# CPU.net
KiCad netlist of a schematic drawn in Altium Designer
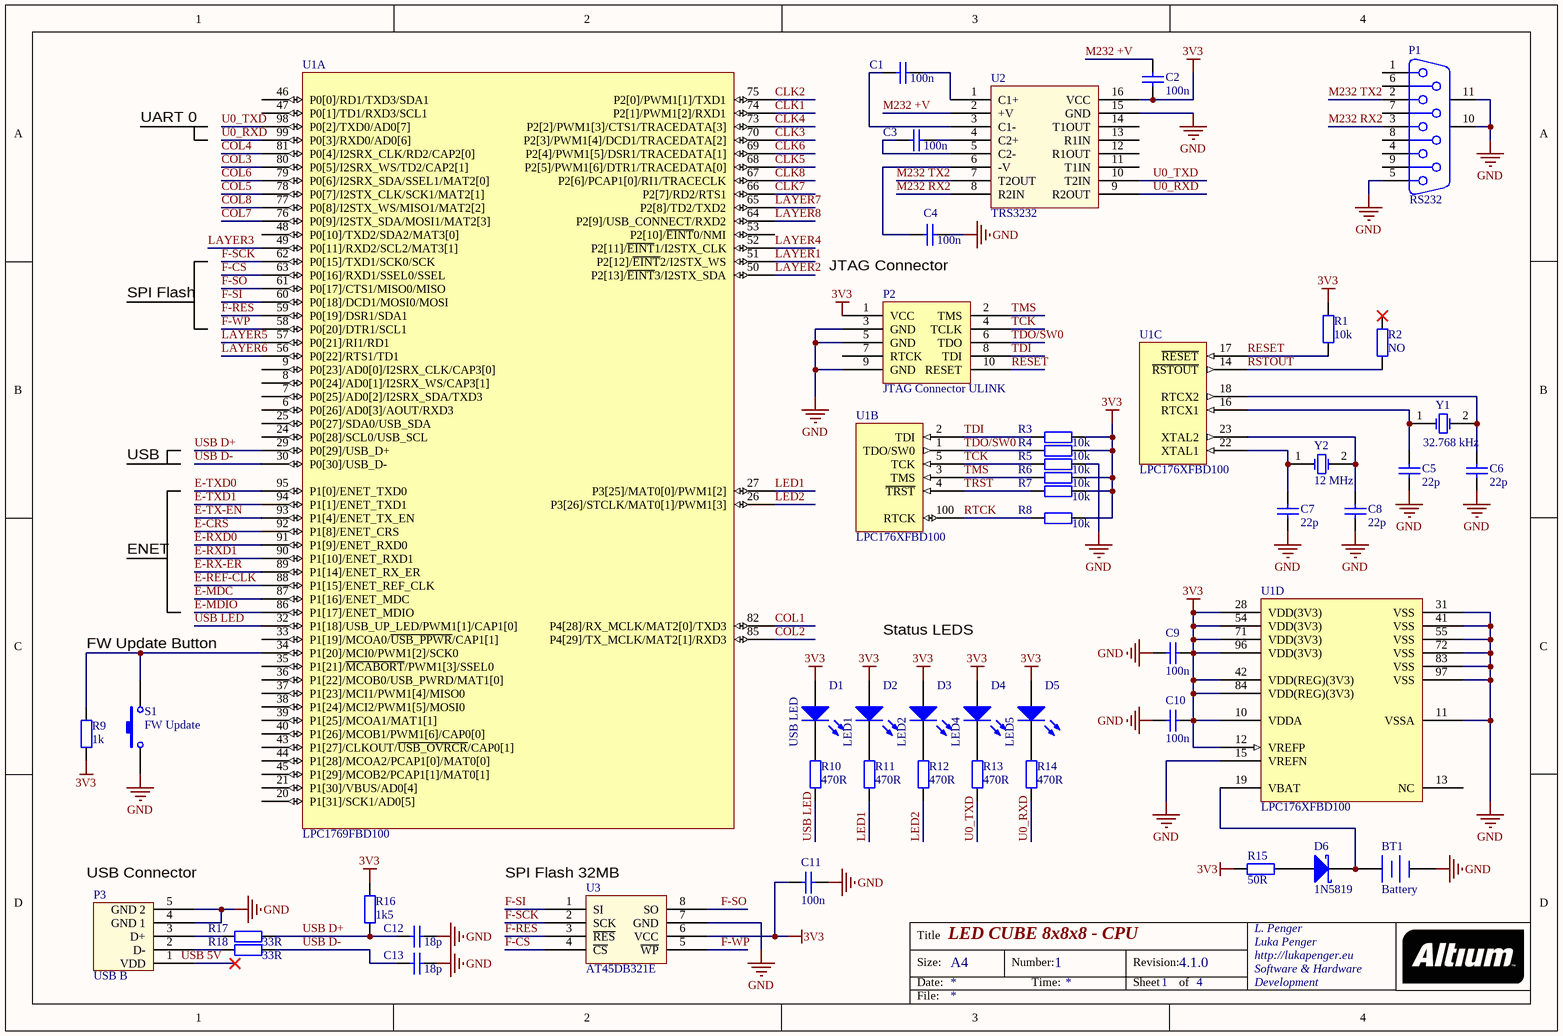
[diagram p0: CPU.SchDoc]

(export (version "E")
  (design (tool "Eeschema 10.0.6"))
  (components
    (comp (ref "BT1")
      (value "Battery")
      (footprint "Battery capacitor")
      (description "Multicell Battery")
      (fields (field (name "PUBLISHER") "Altium Limited"))
      (libsource (lib "Miscellaneous Devices") (part "Battery"))
    )
    (comp (ref "C1")
      (value "100n")
      (footprint "1608[0603]")
      (description "Capacitor")
      (fields (field (name "PUBLISHER") "Altium Limited"))
      (libsource (lib "Miscellaneous Devices") (part "Cap"))
    )
    (comp (ref "C2")
      (value "100n")
      (footprint "1608[0603]")
      (description "Capacitor")
      (fields (field (name "PUBLISHER") "Altium Limited"))
      (libsource (lib "Miscellaneous Devices") (part "Cap"))
    )
    (comp (ref "C3")
      (value "100n")
      (footprint "1608[0603]")
      (description "Capacitor")
      (fields (field (name "PUBLISHER") "Altium Limited"))
      (libsource (lib "Miscellaneous Devices") (part "Cap"))
    )
    (comp (ref "C4")
      (value "100n")
      (footprint "1608[0603]")
      (description "Capacitor")
      (fields (field (name "PUBLISHER") "Altium Limited"))
      (libsource (lib "Miscellaneous Devices") (part "Cap"))
    )
    (comp (ref "C5")
      (value "22p")
      (footprint "1608[0603]")
      (description "Capacitor")
      (fields (field (name "PUBLISHER") "Altium Limited"))
      (libsource (lib "Miscellaneous Devices") (part "Cap"))
    )
    (comp (ref "C6")
      (value "22p")
      (footprint "1608[0603]")
      (description "Capacitor")
      (fields (field (name "PUBLISHER") "Altium Limited"))
      (libsource (lib "Miscellaneous Devices") (part "Cap"))
    )
    (comp (ref "C7")
      (value "22p")
      (footprint "1608[0603]")
      (description "Capacitor")
      (fields (field (name "PUBLISHER") "Altium Limited"))
      (libsource (lib "Miscellaneous Devices") (part "Cap"))
    )
    (comp (ref "C8")
      (value "22p")
      (footprint "1608[0603]")
      (description "Capacitor")
      (fields (field (name "PUBLISHER") "Altium Limited"))
      (libsource (lib "Miscellaneous Devices") (part "Cap"))
    )
    (comp (ref "C9")
      (value "100n")
      (footprint "1608[0603]")
      (description "Capacitor")
      (fields (field (name "PUBLISHER") "Altium Limited"))
      (libsource (lib "Miscellaneous Devices") (part "Cap"))
    )
    (comp (ref "C10")
      (value "100n")
      (footprint "1608[0603]")
      (description "Capacitor")
      (fields (field (name "PUBLISHER") "Altium Limited"))
      (libsource (lib "Miscellaneous Devices") (part "Cap"))
    )
    (comp (ref "C11")
      (value "100n")
      (footprint "1608[0603]")
      (description "Capacitor")
      (fields (field (name "PUBLISHER") "Altium Limited"))
      (libsource (lib "Miscellaneous Devices") (part "Cap"))
    )
    (comp (ref "C12")
      (value "18p")
      (footprint "1608[0603]")
      (description "Capacitor")
      (fields (field (name "PUBLISHER") "Altium Limited"))
      (libsource (lib "Miscellaneous Devices") (part "Cap"))
    )
    (comp (ref "C13")
      (value "18p")
      (footprint "1608[0603]")
      (description "Capacitor")
      (fields (field (name "PUBLISHER") "Altium Limited"))
      (libsource (lib "Miscellaneous Devices") (part "Cap"))
    )
    (comp (ref "D1")
      (value "USB LED")
      (footprint "LED-1")
      (description "Typical INFRARED GaAs LED")
      (fields (field (name "PUBLISHER") "Altium Limited"))
      (libsource (lib "Miscellaneous Devices") (part "LED0"))
    )
    (comp (ref "D2")
      (value "LED1")
      (footprint "LED-1")
      (description "Typical INFRARED GaAs LED")
      (fields (field (name "PUBLISHER") "Altium Limited"))
      (libsource (lib "Miscellaneous Devices") (part "LED0"))
    )
    (comp (ref "D3")
      (value "LED2")
      (footprint "LED-1")
      (description "Typical INFRARED GaAs LED")
      (fields (field (name "PUBLISHER") "Altium Limited"))
      (libsource (lib "Miscellaneous Devices") (part "LED0"))
    )
    (comp (ref "D4")
      (value "LED4")
      (footprint "LED-1")
      (description "Typical INFRARED GaAs LED")
      (fields (field (name "PUBLISHER") "Altium Limited"))
      (libsource (lib "Miscellaneous Devices") (part "LED0"))
    )
    (comp (ref "D5")
      (value "LED5")
      (footprint "LED-1")
      (description "Typical INFRARED GaAs LED")
      (fields (field (name "PUBLISHER") "Altium Limited"))
      (libsource (lib "Miscellaneous Devices") (part "LED0"))
    )
    (comp (ref "D6")
      (value "1N5819")
      (footprint "DO-214AC (SMA)")
      (description "Schottky Diode")
      (fields (field (name "PUBLISHER") "Altium Limited"))
      (libsource (lib "Miscellaneous Devices") (part "D Schottky"))
    )
    (comp (ref "P1")
      (value "RS232")
      (footprint "DSUB1.385-2H9")
      (description "Receptacle Assembly, 9 Position, Right Angle")
      (fields (field (name "PUBLISHER") "Altium Limited"))
      (libsource (lib "Miscellaneous Connectors") (part "D Connector 9"))
    )
    (comp (ref "P2")
      (value "JTAG Connector ULINK")
      (footprint "SMT IDC Header 2X5 10 PIN 1.27mm")
      (description "JTAG Connector")
      (libsource (lib "LP_Lib") (part "JTAG Connector ULINK"))
    )
    (comp (ref "P3")
      (value "USB B")
      (footprint "USB B")
      (description "USB Connector")
      (libsource (lib "LP_Lib") (part "USB B"))
    )
    (comp (ref "R1")
      (value "10k")
      (footprint "1608[0603]")
      (description "Resistor")
      (fields (field (name "PUBLISHER") "Altium Limited"))
      (libsource (lib "Miscellaneous Devices") (part "Res2"))
    )
    (comp (ref "R2")
      (value "NO")
      (footprint "1608[0603]")
      (description "Resistor")
      (fields (field (name "PUBLISHER") "Altium Limited"))
      (libsource (lib "Miscellaneous Devices") (part "Res2"))
    )
    (comp (ref "R3")
      (value "10k")
      (footprint "1608[0603]")
      (description "Resistor")
      (fields (field (name "PUBLISHER") "Altium Limited"))
      (libsource (lib "") (part "Res2_3"))
    )
    (comp (ref "R4")
      (value "10k")
      (footprint "1608[0603]")
      (description "Resistor")
      (fields (field (name "PUBLISHER") "Altium Limited"))
      (libsource (lib "") (part "Res2_3"))
    )
    (comp (ref "R5")
      (value "10k")
      (footprint "1608[0603]")
      (description "Resistor")
      (fields (field (name "PUBLISHER") "Altium Limited"))
      (libsource (lib "") (part "Res2_3"))
    )
    (comp (ref "R6")
      (value "10k")
      (footprint "1608[0603]")
      (description "Resistor")
      (fields (field (name "PUBLISHER") "Altium Limited"))
      (libsource (lib "") (part "Res2_3"))
    )
    (comp (ref "R7")
      (value "10k")
      (footprint "1608[0603]")
      (description "Resistor")
      (fields (field (name "PUBLISHER") "Altium Limited"))
      (libsource (lib "") (part "Res2_3"))
    )
    (comp (ref "R8")
      (value "10k")
      (footprint "1608[0603]")
      (description "Resistor")
      (fields (field (name "PUBLISHER") "Altium Limited"))
      (libsource (lib "") (part "Res2_3"))
    )
    (comp (ref "R9")
      (value "1k")
      (footprint "1608[0603]")
      (description "Resistor")
      (fields (field (name "PUBLISHER") "Altium Limited"))
      (libsource (lib "Miscellaneous Devices") (part "Res2"))
    )
    (comp (ref "R10")
      (value "470R")
      (footprint "1608[0603]")
      (description "Resistor")
      (fields (field (name "PUBLISHER") "Altium Limited"))
      (libsource (lib "Miscellaneous Devices") (part "Res2"))
    )
    (comp (ref "R11")
      (value "470R")
      (footprint "1608[0603]")
      (description "Resistor")
      (fields (field (name "PUBLISHER") "Altium Limited"))
      (libsource (lib "Miscellaneous Devices") (part "Res2"))
    )
    (comp (ref "R12")
      (value "470R")
      (footprint "1608[0603]")
      (description "Resistor")
      (fields (field (name "PUBLISHER") "Altium Limited"))
      (libsource (lib "Miscellaneous Devices") (part "Res2"))
    )
    (comp (ref "R13")
      (value "470R")
      (footprint "1608[0603]")
      (description "Resistor")
      (fields (field (name "PUBLISHER") "Altium Limited"))
      (libsource (lib "Miscellaneous Devices") (part "Res2"))
    )
    (comp (ref "R14")
      (value "470R")
      (footprint "1608[0603]")
      (description "Resistor")
      (fields (field (name "PUBLISHER") "Altium Limited"))
      (libsource (lib "Miscellaneous Devices") (part "Res2"))
    )
    (comp (ref "R15")
      (value "50R")
      (footprint "6-0805_N")
      (description "Resistor")
      (fields (field (name "PUBLISHER") "Altium Limited"))
      (libsource (lib "") (part "Res2_1"))
    )
    (comp (ref "R16")
      (value "1k5")
      (footprint "1608[0603]")
      (description "Resistor")
      (fields (field (name "PUBLISHER") "Altium Limited"))
      (libsource (lib "") (part "Res2_2"))
    )
    (comp (ref "R17")
      (value "33R")
      (footprint "1608[0603]")
      (description "Resistor")
      (fields (field (name "PUBLISHER") "Altium Limited"))
      (libsource (lib "") (part "Res2_1"))
    )
    (comp (ref "R18")
      (value "33R")
      (footprint "1608[0603]")
      (description "Resistor")
      (fields (field (name "PUBLISHER") "Altium Limited"))
      (libsource (lib "") (part "Res2_1"))
    )
    (comp (ref "S1")
      (value "FW Update")
      (footprint "SWITCH-TACTILE-90")
      (description "Switch")
      (fields (field (name "PUBLISHER") "Altium Limited"))
      (libsource (lib "Miscellaneous Devices") (part "SW-PB"))
    )
    (comp (ref "U1")
      (value "LPC176XFBD100")
      (footprint "SOT407-1_N")
      (fields (field (name "PUBLISHER") "Altium Limited"))
      (libsource (lib "") (part "LPC1768FBD100_1"))
    )
    (comp (ref "U2")
      (value "TRS3232")
      (footprint "SOIC16_N")
      (description "Dual 232 +3V3")
      (libsource (lib "LP_Lib") (part "MAX2232"))
    )
    (comp (ref "U3")
      (value "AT45DB321E")
      (footprint "AT45DB321")
      (description "SPI Flash 32MB")
      (libsource (lib "LP_Lib") (part "AT45DB321D"))
    )
    (comp (ref "Y1")
      (value "32.768 kHz")
      (footprint "Crystal FC-135")
      (description "Crystal Oscillator")
      (fields (field (name "PUBLISHER") "Altium Limited"))
      (libsource (lib "Miscellaneous Devices") (part "XTAL"))
    )
    (comp (ref "Y2")
      (value "12 MHz")
      (footprint "5x3.2 Crystal")
      (description "Crystal Oscillator")
      (fields (field (name "PUBLISHER") "Altium Limited"))
      (libsource (lib "Miscellaneous Devices") (part "XTAL"))
    )
  )
  (nets
    (net (code "1") (name "/CLK1") (class "Default")
      (node (ref "U1") (pin "74") (pinfunction "P2[1]/PWM1[2]/RXD1_74") (pintype "bidirectional"))
    )
    (net (code "2") (name "/CLK2") (class "Default")
      (node (ref "U1") (pin "75") (pinfunction "P2[0]/PWM1[1]/TXD1_75") (pintype "bidirectional"))
    )
    (net (code "3") (name "/CLK3") (class "Default")
      (node (ref "U1") (pin "70") (pinfunction "P2[3]/PWM1[4]/DCD1/TRACEDATA[2]_70") (pintype "bidirectional"))
    )
    (net (code "4") (name "/CLK4") (class "Default")
      (node (ref "U1") (pin "73") (pinfunction "P2[2]/PWM1[3]/CTS1/TRACEDATA[3]_73") (pintype "bidirectional"))
    )
    (net (code "5") (name "/CLK5") (class "Default")
      (node (ref "U1") (pin "68") (pinfunction "P2[5]/PWM1[6]/DTR1/TRACEDATA[0]_68") (pintype "bidirectional"))
    )
    (net (code "6") (name "/CLK6") (class "Default")
      (node (ref "U1") (pin "69") (pinfunction "P2[4]/PWM1[5]/DSR1/TRACEDATA[1]_69") (pintype "bidirectional"))
    )
    (net (code "7") (name "/CLK7") (class "Default")
      (node (ref "U1") (pin "66") (pinfunction "P2[7]/RD2/RTS1_66") (pintype "bidirectional"))
    )
    (net (code "8") (name "/CLK8") (class "Default")
      (node (ref "U1") (pin "67") (pinfunction "P2[6]/PCAP1[0]/RI1/TRACECLK_67") (pintype "bidirectional"))
    )
    (net (code "9") (name "/COL1") (class "Default")
      (node (ref "U1") (pin "82") (pinfunction "P4[28]/RX_MCLK/MAT2[0]/TXD3_82") (pintype "bidirectional"))
    )
    (net (code "10") (name "/COL2") (class "Default")
      (node (ref "U1") (pin "85") (pinfunction "P4[29]/TX_MCLK/MAT2[1]/RXD3_85") (pintype "bidirectional"))
    )
    (net (code "11") (name "/COL3") (class "Default")
      (node (ref "U1") (pin "80") (pinfunction "P0[5]/I2SRX_WS/TD2/CAP2[1]_80") (pintype "bidirectional"))
    )
    (net (code "12") (name "/COL4") (class "Default")
      (node (ref "U1") (pin "81") (pinfunction "P0[4]/I2SRX_CLK/RD2/CAP2[0]_81") (pintype "bidirectional"))
    )
    (net (code "13") (name "/COL5") (class "Default")
      (node (ref "U1") (pin "78") (pinfunction "P0[7]/I2STX_CLK/SCK1/MAT2[1]_78") (pintype "bidirectional"))
    )
    (net (code "14") (name "/COL6") (class "Default")
      (node (ref "U1") (pin "79") (pinfunction "P0[6]/I2SRX_SDA/SSEL1/MAT2[0]_79") (pintype "bidirectional"))
    )
    (net (code "15") (name "/COL7") (class "Default")
      (node (ref "U1") (pin "76") (pinfunction "P0[9]/I2STX_SDA/MOSI1/MAT2[3]_76") (pintype "bidirectional"))
    )
    (net (code "16") (name "/COL8") (class "Default")
      (node (ref "U1") (pin "77") (pinfunction "P0[8]/I2STX_WS/MISO1/MAT2[2]_77") (pintype "bidirectional"))
    )
    (net (code "17") (name "/E-CRS") (class "Default")
      (node (ref "U1") (pin "92") (pinfunction "P1[8]/ENET_CRS_92") (pintype "bidirectional"))
    )
    (net (code "18") (name "/E-MDC") (class "Default")
      (node (ref "U1") (pin "87") (pinfunction "P1[16]/ENET_MDC_87") (pintype "bidirectional"))
    )
    (net (code "19") (name "/E-MDIO") (class "Default")
      (node (ref "U1") (pin "86") (pinfunction "P1[17]/ENET_MDIO_86") (pintype "bidirectional"))
    )
    (net (code "20") (name "/E-REF-CLK") (class "Default")
      (node (ref "U1") (pin "88") (pinfunction "P1[15]/ENET_REF_CLK_88") (pintype "bidirectional"))
    )
    (net (code "21") (name "/E-RX-ER") (class "Default")
      (node (ref "U1") (pin "89") (pinfunction "P1[14]/ENET_RX_ER_89") (pintype "bidirectional"))
    )
    (net (code "22") (name "/E-RXD0") (class "Default")
      (node (ref "U1") (pin "91") (pinfunction "P1[9]/ENET_RXD0_91") (pintype "bidirectional"))
    )
    (net (code "23") (name "/E-RXD1") (class "Default")
      (node (ref "U1") (pin "90") (pinfunction "P1[10]/ENET_RXD1_90") (pintype "bidirectional"))
    )
    (net (code "24") (name "/E-TX-EN") (class "Default")
      (node (ref "U1") (pin "93") (pinfunction "P1[4]/ENET_TX_EN_93") (pintype "bidirectional"))
    )
    (net (code "25") (name "/E-TXD0") (class "Default")
      (node (ref "U1") (pin "95") (pinfunction "P1[0]/ENET_TXD0_95") (pintype "bidirectional"))
    )
    (net (code "26") (name "/E-TXD1") (class "Default")
      (node (ref "U1") (pin "94") (pinfunction "P1[1]/ENET_TXD1_94") (pintype "bidirectional"))
    )
    (net (code "27") (name "/F-CS") (class "Default")
      (node (ref "U1") (pin "63") (pinfunction "P0[16]/RXD1/SSEL0/SSEL_63") (pintype "bidirectional"))
      (node (ref "U3") (pin "4") (pinfunction "~{CS}_4") (pintype "passive"))
    )
    (net (code "28") (name "/F-RES") (class "Default")
      (node (ref "U1") (pin "59") (pinfunction "P0[19]/DSR1/SDA1_59") (pintype "bidirectional"))
      (node (ref "U3") (pin "3") (pinfunction "~{RES}_3") (pintype "passive"))
    )
    (net (code "29") (name "/F-SCK") (class "Default")
      (node (ref "U1") (pin "62") (pinfunction "P0[15]/TXD1/SCK0/SCK_62") (pintype "bidirectional"))
      (node (ref "U3") (pin "2") (pinfunction "SCK_2") (pintype "passive"))
    )
    (net (code "30") (name "/F-SI") (class "Default")
      (node (ref "U1") (pin "60") (pinfunction "P0[18]/DCD1/MOSI0/MOSI_60") (pintype "bidirectional"))
      (node (ref "U3") (pin "1") (pinfunction "SI_1") (pintype "passive"))
    )
    (net (code "31") (name "/F-SO") (class "Default")
      (node (ref "U1") (pin "61") (pinfunction "P0[17]/CTS1/MISO0/MISO_61") (pintype "bidirectional"))
      (node (ref "U3") (pin "8") (pinfunction "SO_8") (pintype "passive"))
    )
    (net (code "32") (name "/F-WP") (class "Default")
      (node (ref "U1") (pin "58") (pinfunction "P0[20]/DTR1/SCL1_58") (pintype "bidirectional"))
      (node (ref "U3") (pin "5") (pinfunction "~{WP}_5") (pintype "passive"))
    )
    (net (code "33") (name "/LAYER1") (class "Default")
      (node (ref "U1") (pin "51") (pinfunction "P2[12]/~{EINT}2/I2STX_WS_51") (pintype "bidirectional"))
    )
    (net (code "34") (name "/LAYER2") (class "Default")
      (node (ref "U1") (pin "50") (pinfunction "P2[13]/~{EINT}3/I2STX_SDA_50") (pintype "bidirectional"))
    )
    (net (code "35") (name "/LAYER3") (class "Default")
      (node (ref "U1") (pin "49") (pinfunction "P0[11]/RXD2/SCL2/MAT3[1]_49") (pintype "bidirectional"))
    )
    (net (code "36") (name "/LAYER4") (class "Default")
      (node (ref "U1") (pin "52") (pinfunction "P2[11]/~{EINT}1/I2STX_CLK_52") (pintype "bidirectional"))
    )
    (net (code "37") (name "/LAYER5") (class "Default")
      (node (ref "U1") (pin "57") (pinfunction "P0[21]/RI1/RD1_57") (pintype "bidirectional"))
    )
    (net (code "38") (name "/LAYER6") (class "Default")
      (node (ref "U1") (pin "56") (pinfunction "P0[22]/RTS1/TD1_56") (pintype "bidirectional"))
    )
    (net (code "39") (name "/LAYER7") (class "Default")
      (node (ref "U1") (pin "65") (pinfunction "P2[8]/TD2/TXD2_65") (pintype "bidirectional"))
    )
    (net (code "40") (name "/LAYER8") (class "Default")
      (node (ref "U1") (pin "64") (pinfunction "P2[9]/USB_CONNECT/RXD2_64") (pintype "bidirectional"))
    )
    (net (code "41") (name "/LED1") (class "Default")
      (node (ref "R11") (pin "1") (pinfunction "1_1") (pintype "passive"))
      (node (ref "U1") (pin "27") (pinfunction "P3[25]/MAT0[0]/PWM1[2]_27") (pintype "bidirectional"))
    )
    (net (code "42") (name "/LED2") (class "Default")
      (node (ref "R12") (pin "1") (pinfunction "1_1") (pintype "passive"))
      (node (ref "U1") (pin "26") (pinfunction "P3[26]/STCLK/MAT0[1]/PWM1[3]_26") (pintype "bidirectional"))
    )
    (net (code "43") (name "/M232 +V") (class "Default")
      (node (ref "C2") (pin "1") (pinfunction "1_1") (pintype "passive"))
      (node (ref "U2") (pin "2") (pinfunction "+V_2") (pintype "passive"))
    )
    (net (code "44") (name "/M232 RX2") (class "Default")
      (node (ref "P1") (pin "3") (pinfunction "3_3") (pintype "passive"))
      (node (ref "U2") (pin "8") (pinfunction "R2IN_8") (pintype "passive"))
    )
    (net (code "45") (name "/M232 TX2") (class "Default")
      (node (ref "P1") (pin "2") (pinfunction "2_2") (pintype "passive"))
      (node (ref "U2") (pin "7") (pinfunction "T2OUT_7") (pintype "passive"))
    )
    (net (code "46") (name "/RESET") (class "Default")
      (node (ref "P2") (pin "10") (pinfunction "RESET_10") (pintype "passive"))
      (node (ref "R1") (pin "1") (pinfunction "1_1") (pintype "passive"))
      (node (ref "U1") (pin "17") (pinfunction "~{RESET}_17") (pintype "input"))
    )
    (net (code "47") (name "/RSTOUT") (class "Default")
      (node (ref "R2") (pin "1") (pinfunction "1_1") (pintype "passive"))
      (node (ref "U1") (pin "14") (pinfunction "~{RSTOUT}_14") (pintype "output"))
    )
    (net (code "48") (name "/RTCK") (class "Default")
      (node (ref "R8") (pin "1") (pinfunction "1_1") (pintype "passive"))
      (node (ref "U1") (pin "100") (pinfunction "RTCK_100") (pintype "bidirectional"))
    )
    (net (code "49") (name "/TCK") (class "Default")
      (node (ref "P2") (pin "4") (pinfunction "TCLK_4") (pintype "passive"))
      (node (ref "R5") (pin "1") (pinfunction "1_1") (pintype "passive"))
      (node (ref "U1") (pin "5") (pinfunction "TCK_5") (pintype "input"))
    )
    (net (code "50") (name "/TDI") (class "Default")
      (node (ref "P2") (pin "8") (pinfunction "TDI_8") (pintype "passive"))
      (node (ref "R3") (pin "1") (pinfunction "1_1") (pintype "passive"))
      (node (ref "U1") (pin "2") (pinfunction "TDI_2") (pintype "input"))
    )
    (net (code "51") (name "/TDO{slash}SW0") (class "Default")
      (node (ref "P2") (pin "6") (pinfunction "TDO_6") (pintype "passive"))
      (node (ref "R4") (pin "1") (pinfunction "1_1") (pintype "passive"))
      (node (ref "U1") (pin "1") (pinfunction "TDO/SW0_1") (pintype "output"))
    )
    (net (code "52") (name "/TMS") (class "Default")
      (node (ref "P2") (pin "2") (pinfunction "TMS_2") (pintype "passive"))
      (node (ref "R6") (pin "1") (pinfunction "1_1") (pintype "passive"))
      (node (ref "U1") (pin "3") (pinfunction "TMS_3") (pintype "input"))
    )
    (net (code "53") (name "/TRST") (class "Default")
      (node (ref "R7") (pin "1") (pinfunction "1_1") (pintype "passive"))
      (node (ref "U1") (pin "4") (pinfunction "~{TRST}_4") (pintype "input"))
    )
    (net (code "54") (name "/U0_RXD") (class "Default")
      (node (ref "R14") (pin "1") (pinfunction "1_1") (pintype "passive"))
      (node (ref "U1") (pin "99") (pinfunction "P0[3]/RXD0/AD0[6]_99") (pintype "bidirectional"))
      (node (ref "U2") (pin "9") (pinfunction "R2OUT_9") (pintype "passive"))
    )
    (net (code "55") (name "/U0_TXD") (class "Default")
      (node (ref "R13") (pin "1") (pinfunction "1_1") (pintype "passive"))
      (node (ref "U1") (pin "98") (pinfunction "P0[2]/TXD0/AD0[7]_98") (pintype "bidirectional"))
      (node (ref "U2") (pin "10") (pinfunction "T2IN_10") (pintype "passive"))
    )
    (net (code "57") (name "/USB D+") (class "Default")
      (node (ref "C12") (pin "1") (pinfunction "1_1") (pintype "passive"))
      (node (ref "R16") (pin "2") (pinfunction "2_2") (pintype "passive"))
      (node (ref "R17") (pin "1") (pinfunction "1_1") (pintype "passive"))
      (node (ref "U1") (pin "29") (pinfunction "P0[29]/USB_D+_29") (pintype "bidirectional"))
    )
    (net (code "58") (name "/USB D-") (class "Default")
      (node (ref "C13") (pin "1") (pinfunction "1_1") (pintype "passive"))
      (node (ref "R18") (pin "1") (pinfunction "1_1") (pintype "passive"))
      (node (ref "U1") (pin "30") (pinfunction "P0[30]/USB_D-_30") (pintype "bidirectional"))
    )
    (net (code "59") (name "/USB LED") (class "Default")
      (node (ref "R10") (pin "1") (pinfunction "1_1") (pintype "passive"))
      (node (ref "U1") (pin "32") (pinfunction "P1[18]/USB_UP_LED/PWM1[1]/CAP1[0]_32") (pintype "bidirectional"))
    )
    (net (code "60") (name "3V3") (class "Default")
      (node (ref "C10") (pin "2") (pinfunction "2_2") (pintype "passive"))
      (node (ref "C11") (pin "2") (pinfunction "2_2") (pintype "passive"))
      (node (ref "C2") (pin "2") (pinfunction "2_2") (pintype "passive"))
      (node (ref "C9") (pin "1") (pinfunction "1_1") (pintype "passive"))
      (node (ref "D1") (pin "1") (pinfunction "A_1") (pintype "passive"))
      (node (ref "D2") (pin "1") (pinfunction "A_1") (pintype "passive"))
      (node (ref "D3") (pin "1") (pinfunction "A_1") (pintype "passive"))
      (node (ref "D4") (pin "1") (pinfunction "A_1") (pintype "passive"))
      (node (ref "D5") (pin "1") (pinfunction "A_1") (pintype "passive"))
      (node (ref "P2") (pin "1") (pinfunction "VCC_1") (pintype "passive"))
      (node (ref "R1") (pin "2") (pinfunction "2_2") (pintype "passive"))
      (node (ref "R15") (pin "2") (pinfunction "2_2") (pintype "passive"))
      (node (ref "R16") (pin "1") (pinfunction "1_1") (pintype "passive"))
      (node (ref "R3") (pin "2") (pinfunction "2_2") (pintype "passive"))
      (node (ref "R4") (pin "2") (pinfunction "2_2") (pintype "passive"))
      (node (ref "R6") (pin "2") (pinfunction "2_2") (pintype "passive"))
      (node (ref "R7") (pin "2") (pinfunction "2_2") (pintype "passive"))
      (node (ref "R8") (pin "2") (pinfunction "2_2") (pintype "passive"))
      (node (ref "R9") (pin "1") (pinfunction "1_1") (pintype "passive"))
      (node (ref "U1") (pin "10") (pinfunction "VDDA_10") (pintype "power_in"))
      (node (ref "U1") (pin "12") (pinfunction "VREFP_12") (pintype "input"))
      (node (ref "U1") (pin "28") (pinfunction "VDD(3V3)_28") (pintype "power_in"))
      (node (ref "U1") (pin "42") (pinfunction "VDD(REG)(3V3)_42") (pintype "power_in"))
      (node (ref "U1") (pin "54") (pinfunction "VDD(3V3)_54") (pintype "power_in"))
      (node (ref "U1") (pin "71") (pinfunction "VDD(3V3)_71") (pintype "power_in"))
      (node (ref "U1") (pin "84") (pinfunction "VDD(REG)(3V3)_84") (pintype "power_in"))
      (node (ref "U1") (pin "96") (pinfunction "VDD(3V3)_96") (pintype "power_in"))
      (node (ref "U2") (pin "16") (pinfunction "VCC_16") (pintype "passive"))
      (node (ref "U3") (pin "6") (pinfunction "VCC_6") (pintype "passive"))
    )
    (net (code "61") (name "GND") (class "Default")
      (node (ref "BT1") (pin "2") (pinfunction "-_2") (pintype "passive"))
      (node (ref "C10") (pin "1") (pinfunction "1_1") (pintype "passive"))
      (node (ref "C11") (pin "1") (pinfunction "1_1") (pintype "passive"))
      (node (ref "C12") (pin "2") (pinfunction "2_2") (pintype "passive"))
      (node (ref "C13") (pin "2") (pinfunction "2_2") (pintype "passive"))
      (node (ref "C4") (pin "1") (pinfunction "1_1") (pintype "passive"))
      (node (ref "C5") (pin "1") (pinfunction "1_1") (pintype "passive"))
      (node (ref "C6") (pin "1") (pinfunction "1_1") (pintype "passive"))
      (node (ref "C7") (pin "1") (pinfunction "1_1") (pintype "passive"))
      (node (ref "C8") (pin "1") (pinfunction "1_1") (pintype "passive"))
      (node (ref "C9") (pin "2") (pinfunction "2_2") (pintype "passive"))
      (node (ref "P1") (pin "10") (pinfunction "MH1_10") (pintype "passive"))
      (node (ref "P1") (pin "11") (pinfunction "MH2_11") (pintype "passive"))
      (node (ref "P1") (pin "5") (pinfunction "5_5") (pintype "passive"))
      (node (ref "P2") (pin "3") (pinfunction "GND_3") (pintype "passive"))
      (node (ref "P2") (pin "5") (pinfunction "GND_5") (pintype "passive"))
      (node (ref "P2") (pin "9") (pinfunction "GND_9") (pintype "passive"))
      (node (ref "P3") (pin "4") (pinfunction "GND_1_4") (pintype "passive"))
      (node (ref "P3") (pin "5") (pinfunction "GND_2_5") (pintype "passive"))
      (node (ref "R5") (pin "2") (pinfunction "2_2") (pintype "passive"))
      (node (ref "S1") (pin "1") (pinfunction "1_1") (pintype "passive"))
      (node (ref "U1") (pin "11") (pinfunction "VSSA_11") (pintype "power_in"))
      (node (ref "U1") (pin "15") (pinfunction "VREFN_15") (pintype "power_in"))
      (node (ref "U1") (pin "31") (pinfunction "VSS_31") (pintype "power_in"))
      (node (ref "U1") (pin "41") (pinfunction "VSS_41") (pintype "power_in"))
      (node (ref "U1") (pin "55") (pinfunction "VSS_55") (pintype "power_in"))
      (node (ref "U1") (pin "72") (pinfunction "VSS_72") (pintype "power_in"))
      (node (ref "U1") (pin "83") (pinfunction "VSS_83") (pintype "power_in"))
      (node (ref "U1") (pin "97") (pinfunction "VSS_97") (pintype "power_in"))
      (node (ref "U2") (pin "15") (pinfunction "GND_15") (pintype "passive"))
      (node (ref "U3") (pin "7") (pinfunction "GND_7") (pintype "passive"))
    )
    (net (code "62") (name "Net-(BT1-+)") (class "Default")
      (node (ref "BT1") (pin "1") (pinfunction "+_1") (pintype "passive"))
      (node (ref "D6") (pin "2") (pinfunction "K_2") (pintype "passive"))
      (node (ref "U1") (pin "19") (pinfunction "VBAT_19") (pintype "power_in"))
    )
    (net (code "63") (name "Net-(D1-K)") (class "Default")
      (node (ref "D1") (pin "2") (pinfunction "K_2") (pintype "passive"))
      (node (ref "R10") (pin "2") (pinfunction "2_2") (pintype "passive"))
    )
    (net (code "64") (name "Net-(D2-K)") (class "Default")
      (node (ref "D2") (pin "2") (pinfunction "K_2") (pintype "passive"))
      (node (ref "R11") (pin "2") (pinfunction "2_2") (pintype "passive"))
    )
    (net (code "65") (name "Net-(D3-K)") (class "Default")
      (node (ref "D3") (pin "2") (pinfunction "K_2") (pintype "passive"))
      (node (ref "R12") (pin "2") (pinfunction "2_2") (pintype "passive"))
    )
    (net (code "66") (name "Net-(D4-K)") (class "Default")
      (node (ref "D4") (pin "2") (pinfunction "K_2") (pintype "passive"))
      (node (ref "R13") (pin "2") (pinfunction "2_2") (pintype "passive"))
    )
    (net (code "67") (name "Net-(D5-K)") (class "Default")
      (node (ref "D5") (pin "2") (pinfunction "K_2") (pintype "passive"))
      (node (ref "R14") (pin "2") (pinfunction "2_2") (pintype "passive"))
    )
    (net (code "68") (name "Net-(D6-A)") (class "Default")
      (node (ref "D6") (pin "1") (pinfunction "A_1") (pintype "passive"))
      (node (ref "R15") (pin "1") (pinfunction "1_1") (pintype "passive"))
    )
    (net (code "69") (name "Net-(P3-D+)") (class "Default")
      (node (ref "P3") (pin "3") (pinfunction "D+_3") (pintype "passive"))
      (node (ref "R17") (pin "2") (pinfunction "2_2") (pintype "passive"))
    )
    (net (code "70") (name "Net-(P3-D-)") (class "Default")
      (node (ref "P3") (pin "2") (pinfunction "D-_2") (pintype "passive"))
      (node (ref "R18") (pin "2") (pinfunction "2_2") (pintype "passive"))
    )
    (net (code "71") (name "Net-(U1A-P1[20]{slash}MCI0{slash}PWM1[2]{slash}SCK0)") (class "Default")
      (node (ref "R9") (pin "2") (pinfunction "2_2") (pintype "passive"))
      (node (ref "S1") (pin "2") (pinfunction "2_2") (pintype "passive"))
      (node (ref "U1") (pin "34") (pinfunction "P1[20]/MCI0/PWM1[2]/SCK0_34") (pintype "bidirectional"))
    )
    (net (code "72") (name "Net-(U1C-RTCX1)") (class "Default")
      (node (ref "C5") (pin "2") (pinfunction "2_2") (pintype "passive"))
      (node (ref "U1") (pin "16") (pinfunction "RTCX1_16") (pintype "input"))
      (node (ref "Y1") (pin "1") (pinfunction "OSC1_1") (pintype "passive"))
    )
    (net (code "73") (name "Net-(U1C-RTCX2)") (class "Default")
      (node (ref "C6") (pin "2") (pinfunction "2_2") (pintype "passive"))
      (node (ref "U1") (pin "18") (pinfunction "RTCX2_18") (pintype "output"))
      (node (ref "Y1") (pin "2") (pinfunction "OSC2_2") (pintype "passive"))
    )
    (net (code "74") (name "Net-(U1C-XTAL1)") (class "Default")
      (node (ref "C7") (pin "2") (pinfunction "2_2") (pintype "passive"))
      (node (ref "U1") (pin "22") (pinfunction "XTAL1_22") (pintype "input"))
      (node (ref "Y2") (pin "1") (pinfunction "OSC1_1") (pintype "passive"))
    )
    (net (code "75") (name "Net-(U1C-XTAL2)") (class "Default")
      (node (ref "C8") (pin "2") (pinfunction "2_2") (pintype "passive"))
      (node (ref "U1") (pin "23") (pinfunction "XTAL2_23") (pintype "output"))
      (node (ref "Y2") (pin "2") (pinfunction "OSC2_2") (pintype "passive"))
    )
    (net (code "76") (name "Net-(U2--V)") (class "Default")
      (node (ref "C4") (pin "2") (pinfunction "2_2") (pintype "passive"))
      (node (ref "U2") (pin "6") (pinfunction "-V_6") (pintype "passive"))
    )
    (net (code "77") (name "Net-(U2-C1+)") (class "Default")
      (node (ref "C1") (pin "2") (pinfunction "2_2") (pintype "passive"))
      (node (ref "U2") (pin "1") (pinfunction "C1+_1") (pintype "passive"))
    )
    (net (code "78") (name "Net-(U2-C1-)") (class "Default")
      (node (ref "C1") (pin "1") (pinfunction "1_1") (pintype "passive"))
      (node (ref "U2") (pin "3") (pinfunction "C1-_3") (pintype "passive"))
    )
    (net (code "79") (name "Net-(U2-C2+)") (class "Default")
      (node (ref "C3") (pin "2") (pinfunction "2_2") (pintype "passive"))
      (node (ref "U2") (pin "4") (pinfunction "C2+_4") (pintype "passive"))
    )
    (net (code "80") (name "Net-(U2-C2-)") (class "Default")
      (node (ref "C3") (pin "1") (pinfunction "1_1") (pintype "passive"))
      (node (ref "U2") (pin "5") (pinfunction "C2-_5") (pintype "passive"))
    )
    (net (code "81") (name "unconnected-(P1-Pad1)") (class "Default")
      (node (ref "P1") (pin "1") (pinfunction "1_1") (pintype "passive"))
    )
    (net (code "82") (name "unconnected-(P1-Pad4)") (class "Default")
      (node (ref "P1") (pin "4") (pinfunction "4_4") (pintype "passive"))
    )
    (net (code "83") (name "unconnected-(P1-Pad6)") (class "Default")
      (node (ref "P1") (pin "6") (pinfunction "6_6") (pintype "passive"))
    )
    (net (code "84") (name "unconnected-(P1-Pad7)") (class "Default")
      (node (ref "P1") (pin "7") (pinfunction "7_7") (pintype "passive"))
    )
    (net (code "85") (name "unconnected-(P1-Pad8)") (class "Default")
      (node (ref "P1") (pin "8") (pinfunction "8_8") (pintype "passive"))
    )
    (net (code "86") (name "unconnected-(P1-Pad9)") (class "Default")
      (node (ref "P1") (pin "9") (pinfunction "9_9") (pintype "passive"))
    )
    (net (code "87") (name "unconnected-(P2-RTCK-Pad7)") (class "Default")
      (node (ref "P2") (pin "7") (pinfunction "RTCK_7") (pintype "passive"))
    )
    (net (code "88") (name "unconnected-(P3-VDD-Pad1)") (class "Default")
      (node (ref "P3") (pin "1") (pinfunction "VDD_1") (pintype "passive+no_connect"))
    )
    (net (code "89") (name "unconnected-(R2-Pad2)") (class "Default")
      (node (ref "R2") (pin "2") (pinfunction "2_2") (pintype "passive+no_connect"))
    )
    (net (code "90") (name "unconnected-(U1A-P0[0]{slash}RD1{slash}TXD3{slash}SDA1-Pad46)") (class "Default")
      (node (ref "U1") (pin "46") (pinfunction "P0[0]/RD1/TXD3/SDA1_46") (pintype "bidirectional"))
    )
    (net (code "91") (name "unconnected-(U1A-P0[1]{slash}TD1{slash}RXD3{slash}SCL1-Pad47)") (class "Default")
      (node (ref "U1") (pin "47") (pinfunction "P0[1]/TD1/RXD3/SCL1_47") (pintype "bidirectional"))
    )
    (net (code "92") (name "unconnected-(U1A-P0[10]{slash}TXD2{slash}SDA2{slash}MAT3[0]-Pad48)") (class "Default")
      (node (ref "U1") (pin "48") (pinfunction "P0[10]/TXD2/SDA2/MAT3[0]_48") (pintype "bidirectional"))
    )
    (net (code "93") (name "unconnected-(U1A-P0[23]{slash}AD0[0]{slash}I2SRX_CLK{slash}CAP3[0]-Pad9)") (class "Default")
      (node (ref "U1") (pin "9") (pinfunction "P0[23]/AD0[0]/I2SRX_CLK/CAP3[0]_9") (pintype "bidirectional"))
    )
    (net (code "94") (name "unconnected-(U1A-P0[24]{slash}AD0[1]{slash}I2SRX_WS{slash}CAP3[1]-Pad8)") (class "Default")
      (node (ref "U1") (pin "8") (pinfunction "P0[24]/AD0[1]/I2SRX_WS/CAP3[1]_8") (pintype "bidirectional"))
    )
    (net (code "95") (name "unconnected-(U1A-P0[25]{slash}AD0[2]{slash}I2SRX_SDA{slash}TXD3-Pad7)") (class "Default")
      (node (ref "U1") (pin "7") (pinfunction "P0[25]/AD0[2]/I2SRX_SDA/TXD3_7") (pintype "bidirectional"))
    )
    (net (code "96") (name "unconnected-(U1A-P0[26]{slash}AD0[3]{slash}AOUT{slash}RXD3-Pad6)") (class "Default")
      (node (ref "U1") (pin "6") (pinfunction "P0[26]/AD0[3]/AOUT/RXD3_6") (pintype "bidirectional"))
    )
    (net (code "97") (name "unconnected-(U1A-P0[27]{slash}SDA0{slash}USB_SDA-Pad25)") (class "Default")
      (node (ref "U1") (pin "25") (pinfunction "P0[27]/SDA0/USB_SDA_25") (pintype "bidirectional"))
    )
    (net (code "98") (name "unconnected-(U1A-P0[28]{slash}SCL0{slash}USB_SCL-Pad24)") (class "Default")
      (node (ref "U1") (pin "24") (pinfunction "P0[28]/SCL0/USB_SCL_24") (pintype "bidirectional"))
    )
    (net (code "99") (name "unconnected-(U1A-P1[19]{slash}MCOA0{slash}~{USB_PPWR}{slash}CAP1[1]-Pad33)") (class "Default")
      (node (ref "U1") (pin "33") (pinfunction "P1[19]/MCOA0/~{USB_PPWR}/CAP1[1]_33") (pintype "bidirectional"))
    )
    (net (code "100") (name "unconnected-(U1A-P1[21]{slash}~{MCABORT}{slash}PWM1[3]{slash}SSEL0-Pad35)") (class "Default")
      (node (ref "U1") (pin "35") (pinfunction "P1[21]/~{MCABORT}/PWM1[3]/SSEL0_35") (pintype "bidirectional"))
    )
    (net (code "101") (name "unconnected-(U1A-P1[22]{slash}MCOB0{slash}USB_PWRD{slash}MAT1[0]-Pad36)") (class "Default")
      (node (ref "U1") (pin "36") (pinfunction "P1[22]/MCOB0/USB_PWRD/MAT1[0]_36") (pintype "bidirectional"))
    )
    (net (code "102") (name "unconnected-(U1A-P1[23]{slash}MCI1{slash}PWM1[4]{slash}MISO0-Pad37)") (class "Default")
      (node (ref "U1") (pin "37") (pinfunction "P1[23]/MCI1/PWM1[4]/MISO0_37") (pintype "bidirectional"))
    )
    (net (code "103") (name "unconnected-(U1A-P1[24]{slash}MCI2{slash}PWM1[5]{slash}MOSI0-Pad38)") (class "Default")
      (node (ref "U1") (pin "38") (pinfunction "P1[24]/MCI2/PWM1[5]/MOSI0_38") (pintype "bidirectional"))
    )
    (net (code "104") (name "unconnected-(U1A-P1[25]{slash}MCOA1{slash}MAT1[1]-Pad39)") (class "Default")
      (node (ref "U1") (pin "39") (pinfunction "P1[25]/MCOA1/MAT1[1]_39") (pintype "bidirectional"))
    )
    (net (code "105") (name "unconnected-(U1A-P1[26]{slash}MCOB1{slash}PWM1[6]{slash}CAP0[0]-Pad40)") (class "Default")
      (node (ref "U1") (pin "40") (pinfunction "P1[26]/MCOB1/PWM1[6]/CAP0[0]_40") (pintype "bidirectional"))
    )
    (net (code "106") (name "unconnected-(U1A-P1[27]{slash}CLKOUT{slash}~{USB_OVRCR}{slash}CAP0[1]-Pad43)") (class "Default")
      (node (ref "U1") (pin "43") (pinfunction "P1[27]/CLKOUT/~{USB_OVRCR}/CAP0[1]_43") (pintype "bidirectional"))
    )
    (net (code "107") (name "unconnected-(U1A-P1[28]{slash}MCOA2{slash}PCAP1[0]{slash}MAT0[0]-Pad44)") (class "Default")
      (node (ref "U1") (pin "44") (pinfunction "P1[28]/MCOA2/PCAP1[0]/MAT0[0]_44") (pintype "bidirectional"))
    )
    (net (code "108") (name "unconnected-(U1A-P1[29]{slash}MCOB2{slash}PCAP1[1]{slash}MAT0[1]-Pad45)") (class "Default")
      (node (ref "U1") (pin "45") (pinfunction "P1[29]/MCOB2/PCAP1[1]/MAT0[1]_45") (pintype "bidirectional"))
    )
    (net (code "109") (name "unconnected-(U1A-P1[30]{slash}VBUS{slash}AD0[4]-Pad21)") (class "Default")
      (node (ref "U1") (pin "21") (pinfunction "P1[30]/VBUS/AD0[4]_21") (pintype "bidirectional"))
    )
    (net (code "110") (name "unconnected-(U1A-P1[31]{slash}SCK1{slash}AD0[5]-Pad20)") (class "Default")
      (node (ref "U1") (pin "20") (pinfunction "P1[31]/SCK1/AD0[5]_20") (pintype "bidirectional"))
    )
    (net (code "111") (name "unconnected-(U1A-P2[10]{slash}~{EINT}0{slash}NMI-Pad53)") (class "Default")
      (node (ref "U1") (pin "53") (pinfunction "P2[10]/~{EINT}0/NMI_53") (pintype "bidirectional"))
    )
    (net (code "112") (name "unconnected-(U1D-NC-Pad13)") (class "Default")
      (node (ref "U1") (pin "13") (pinfunction "NC_13") (pintype "power_in"))
    )
    (net (code "113") (name "unconnected-(U2-R1IN-Pad13)") (class "Default")
      (node (ref "U2") (pin "13") (pinfunction "R1IN_13") (pintype "passive"))
    )
    (net (code "114") (name "unconnected-(U2-R1OUT-Pad12)") (class "Default")
      (node (ref "U2") (pin "12") (pinfunction "R1OUT_12") (pintype "passive"))
    )
    (net (code "115") (name "unconnected-(U2-T1IN-Pad11)") (class "Default")
      (node (ref "U2") (pin "11") (pinfunction "T1IN_11") (pintype "passive"))
    )
    (net (code "116") (name "unconnected-(U2-T1OUT-Pad14)") (class "Default")
      (node (ref "U2") (pin "14") (pinfunction "T1OUT_14") (pintype "passive"))
    )
  )
)
